# 02_PowerSupply.net
KiCad netlist of a schematic drawn in Altium Designer
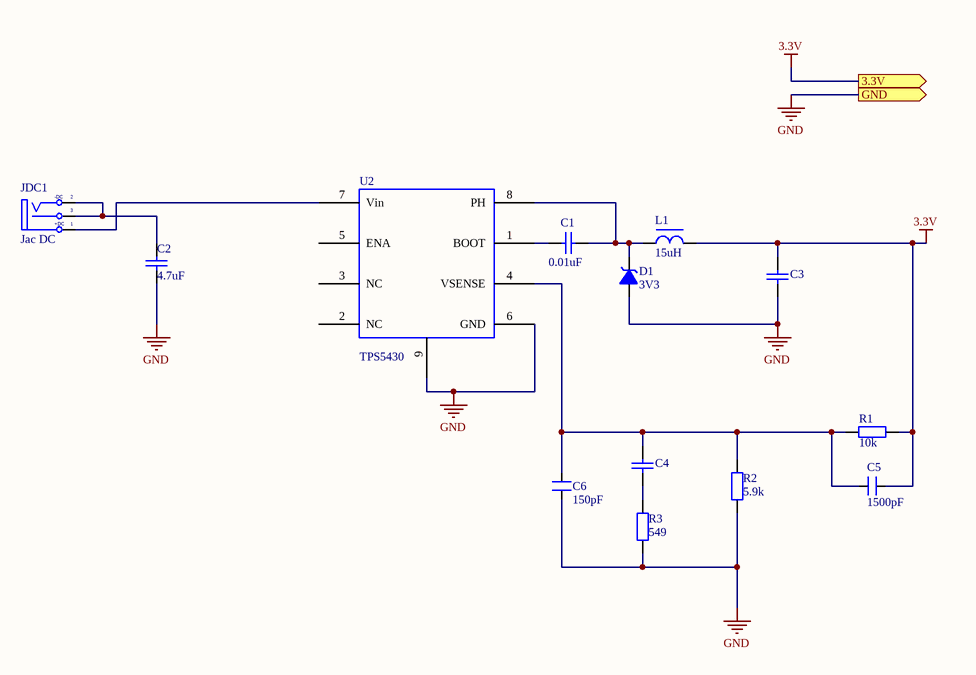
[diagram p0: 02_PowerSupply.SchDoc]

(export (version "E")
  (design (tool "Eeschema 10.0.6"))
  (components
    (comp (ref "C1")
      (value "0.01uF")
      (footprint "C0805")
      (description "Capacitor")
      (fields (field (name "PUBLISHER") "Altium Limited"))
      (libsource (lib "My Library") (part "CapSMD"))
    )
    (comp (ref "C2")
      (value "4.7uF")
      (footprint "C0805")
      (description "Capacitor")
      (fields (field (name "PUBLISHER") "Altium Limited"))
      (libsource (lib "My Library") (part "CapSMD"))
    )
    (comp (ref "C3")
      (value "Capacitor Ceramic")
      (footprint "C0805")
      (description "Capacitor")
      (fields (field (name "PUBLISHER") "Altium Limited"))
      (libsource (lib "My Library") (part "CapSMD"))
    )
    (comp (ref "C4")
      (value "Capacitor Ceramic")
      (footprint "C0805")
      (description "Capacitor")
      (fields (field (name "PUBLISHER") "Altium Limited"))
      (libsource (lib "My Library") (part "CapSMD"))
    )
    (comp (ref "C5")
      (value "1500pF")
      (footprint "CN1")
      (description "Cap np  1pF - 472pF")
      (libsource (lib "My Library") (part "CN1"))
    )
    (comp (ref "C6")
      (value "150pF")
      (footprint "CN1")
      (description "Cap np  1pF - 472pF")
      (libsource (lib "My Library") (part "CN1"))
    )
    (comp (ref "D1")
      (value "3V3")
      (footprint "DZ0.5A")
      (description "Diode Zenner")
      (libsource (lib "My Library") (part "DZ"))
    )
    (comp (ref "JDC1")
      (value "Jac DC")
      (footprint "DC-IN")
      (description "Jac DC input")
      (libsource (lib "My Library") (part "DCIN"))
    )
    (comp (ref "L1")
      (value "15uH")
      (footprint "L-DIP-M-5.3")
      (description "Inductor")
      (libsource (lib "My Library") (part "L-DIP-1"))
    )
    (comp (ref "R1")
      (value "10k")
      (footprint "DIEN TRO 0805")
      (description "Resistor SMD 0805")
      (fields (field (name "Comment") "R0805") (field (name "PUBLISHER") "Altium Limited"))
      (libsource (lib "") (part "R0805_1"))
    )
    (comp (ref "R2")
      (value "5.9k")
      (footprint "DIEN TRO 0805")
      (description "Resistor SMD 0805")
      (fields (field (name "PUBLISHER") "Altium Limited"))
      (libsource (lib "My Library") (part "R0805"))
    )
    (comp (ref "R3")
      (value "549")
      (footprint "DIEN TRO 0805")
      (description "Resistor SMD 0805")
      (fields (field (name "Comment") "R0805") (field (name "PUBLISHER") "Altium Limited"))
      (libsource (lib "My Library") (part "R0805"))
    )
    (comp (ref "U2")
      (value "TPS5430")
      (footprint "TPS5430-2")
      (fields (field (name "NAME") "TPS5430"))
      (libsource (lib "My Library") (part "TPS5430"))
    )
  )
  (nets
    (net (code "1") (name "3.3V") (class "Default")
      (node (ref "C3") (pin "2") (pinfunction "2_2") (pintype "passive"))
      (node (ref "C5") (pin "2") (pinfunction "2_2") (pintype "passive"))
      (node (ref "L1") (pin "2") (pinfunction "2_2") (pintype "passive"))
      (node (ref "R1") (pin "2") (pinfunction "2_2") (pintype "passive"))
    )
    (net (code "2") (name "GND") (class "Default")
      (node (ref "C2") (pin "1") (pinfunction "1_1") (pintype "passive"))
      (node (ref "C3") (pin "1") (pinfunction "1_1") (pintype "passive"))
      (node (ref "C6") (pin "1") (pinfunction "1_1") (pintype "passive"))
      (node (ref "D1") (pin "1") (pinfunction "A_1") (pintype "passive"))
      (node (ref "R2") (pin "1") (pinfunction "1_1") (pintype "passive"))
      (node (ref "R3") (pin "1") (pinfunction "1_1") (pintype "passive"))
      (node (ref "U2") (pin "6") (pinfunction "GND_6") (pintype "passive"))
      (node (ref "U2") (pin "9") (pinfunction "PWR_PAD_9") (pintype "passive"))
    )
    (net (code "3") (name "Net-(C4-Pad1)") (class "Default")
      (node (ref "C4") (pin "1") (pinfunction "1_1") (pintype "passive"))
      (node (ref "R3") (pin "2") (pinfunction "2_2") (pintype "passive"))
    )
    (net (code "4") (name "Net-(D1-K)") (class "Default")
      (node (ref "C1") (pin "1") (pinfunction "1_1") (pintype "passive"))
      (node (ref "D1") (pin "2") (pinfunction "K_2") (pintype "passive"))
      (node (ref "L1") (pin "1") (pinfunction "1_1") (pintype "passive"))
      (node (ref "U2") (pin "8") (pinfunction "PH_8") (pintype "passive"))
    )
    (net (code "5") (name "Net-(JDC1-S)") (class "Default")
      (node (ref "C2") (pin "2") (pinfunction "2_2") (pintype "passive"))
      (node (ref "JDC1") (pin "2") (pinfunction "TN_2") (pintype "passive"))
      (node (ref "JDC1") (pin "3") (pinfunction "S_3") (pintype "power_in"))
    )
    (net (code "6") (name "Net-(JDC1-T)") (class "Default")
      (node (ref "JDC1") (pin "1") (pinfunction "T_1") (pintype "passive"))
      (node (ref "U2") (pin "7") (pinfunction "Vin_7") (pintype "passive"))
    )
    (net (code "7") (name "Net-(U2-BOOT)") (class "Default")
      (node (ref "C1") (pin "2") (pinfunction "2_2") (pintype "passive"))
      (node (ref "U2") (pin "1") (pinfunction "BOOT_1") (pintype "passive"))
    )
    (net (code "8") (name "Net-(U2-VSENSE)") (class "Default")
      (node (ref "C4") (pin "2") (pinfunction "2_2") (pintype "passive"))
      (node (ref "C5") (pin "1") (pinfunction "1_1") (pintype "passive"))
      (node (ref "C6") (pin "2") (pinfunction "2_2") (pintype "passive"))
      (node (ref "R1") (pin "1") (pinfunction "1_1") (pintype "passive"))
      (node (ref "R2") (pin "2") (pinfunction "2_2") (pintype "passive"))
      (node (ref "U2") (pin "4") (pinfunction "VSENSE_4") (pintype "passive"))
    )
    (net (code "9") (name "unconnected-(U2-ENA-Pad5)") (class "Default")
      (node (ref "U2") (pin "5") (pinfunction "ENA_5") (pintype "passive"))
    )
    (net (code "10") (name "unconnected-(U2-NC-Pad2)") (class "Default")
      (node (ref "U2") (pin "2") (pinfunction "NC_2") (pintype "passive"))
    )
    (net (code "11") (name "unconnected-(U2-NC-Pad3)") (class "Default")
      (node (ref "U2") (pin "3") (pinfunction "NC_3") (pintype "passive"))
    )
  )
)
